# FPGA-2.net
KiCad netlist of a schematic drawn in Altium Designer
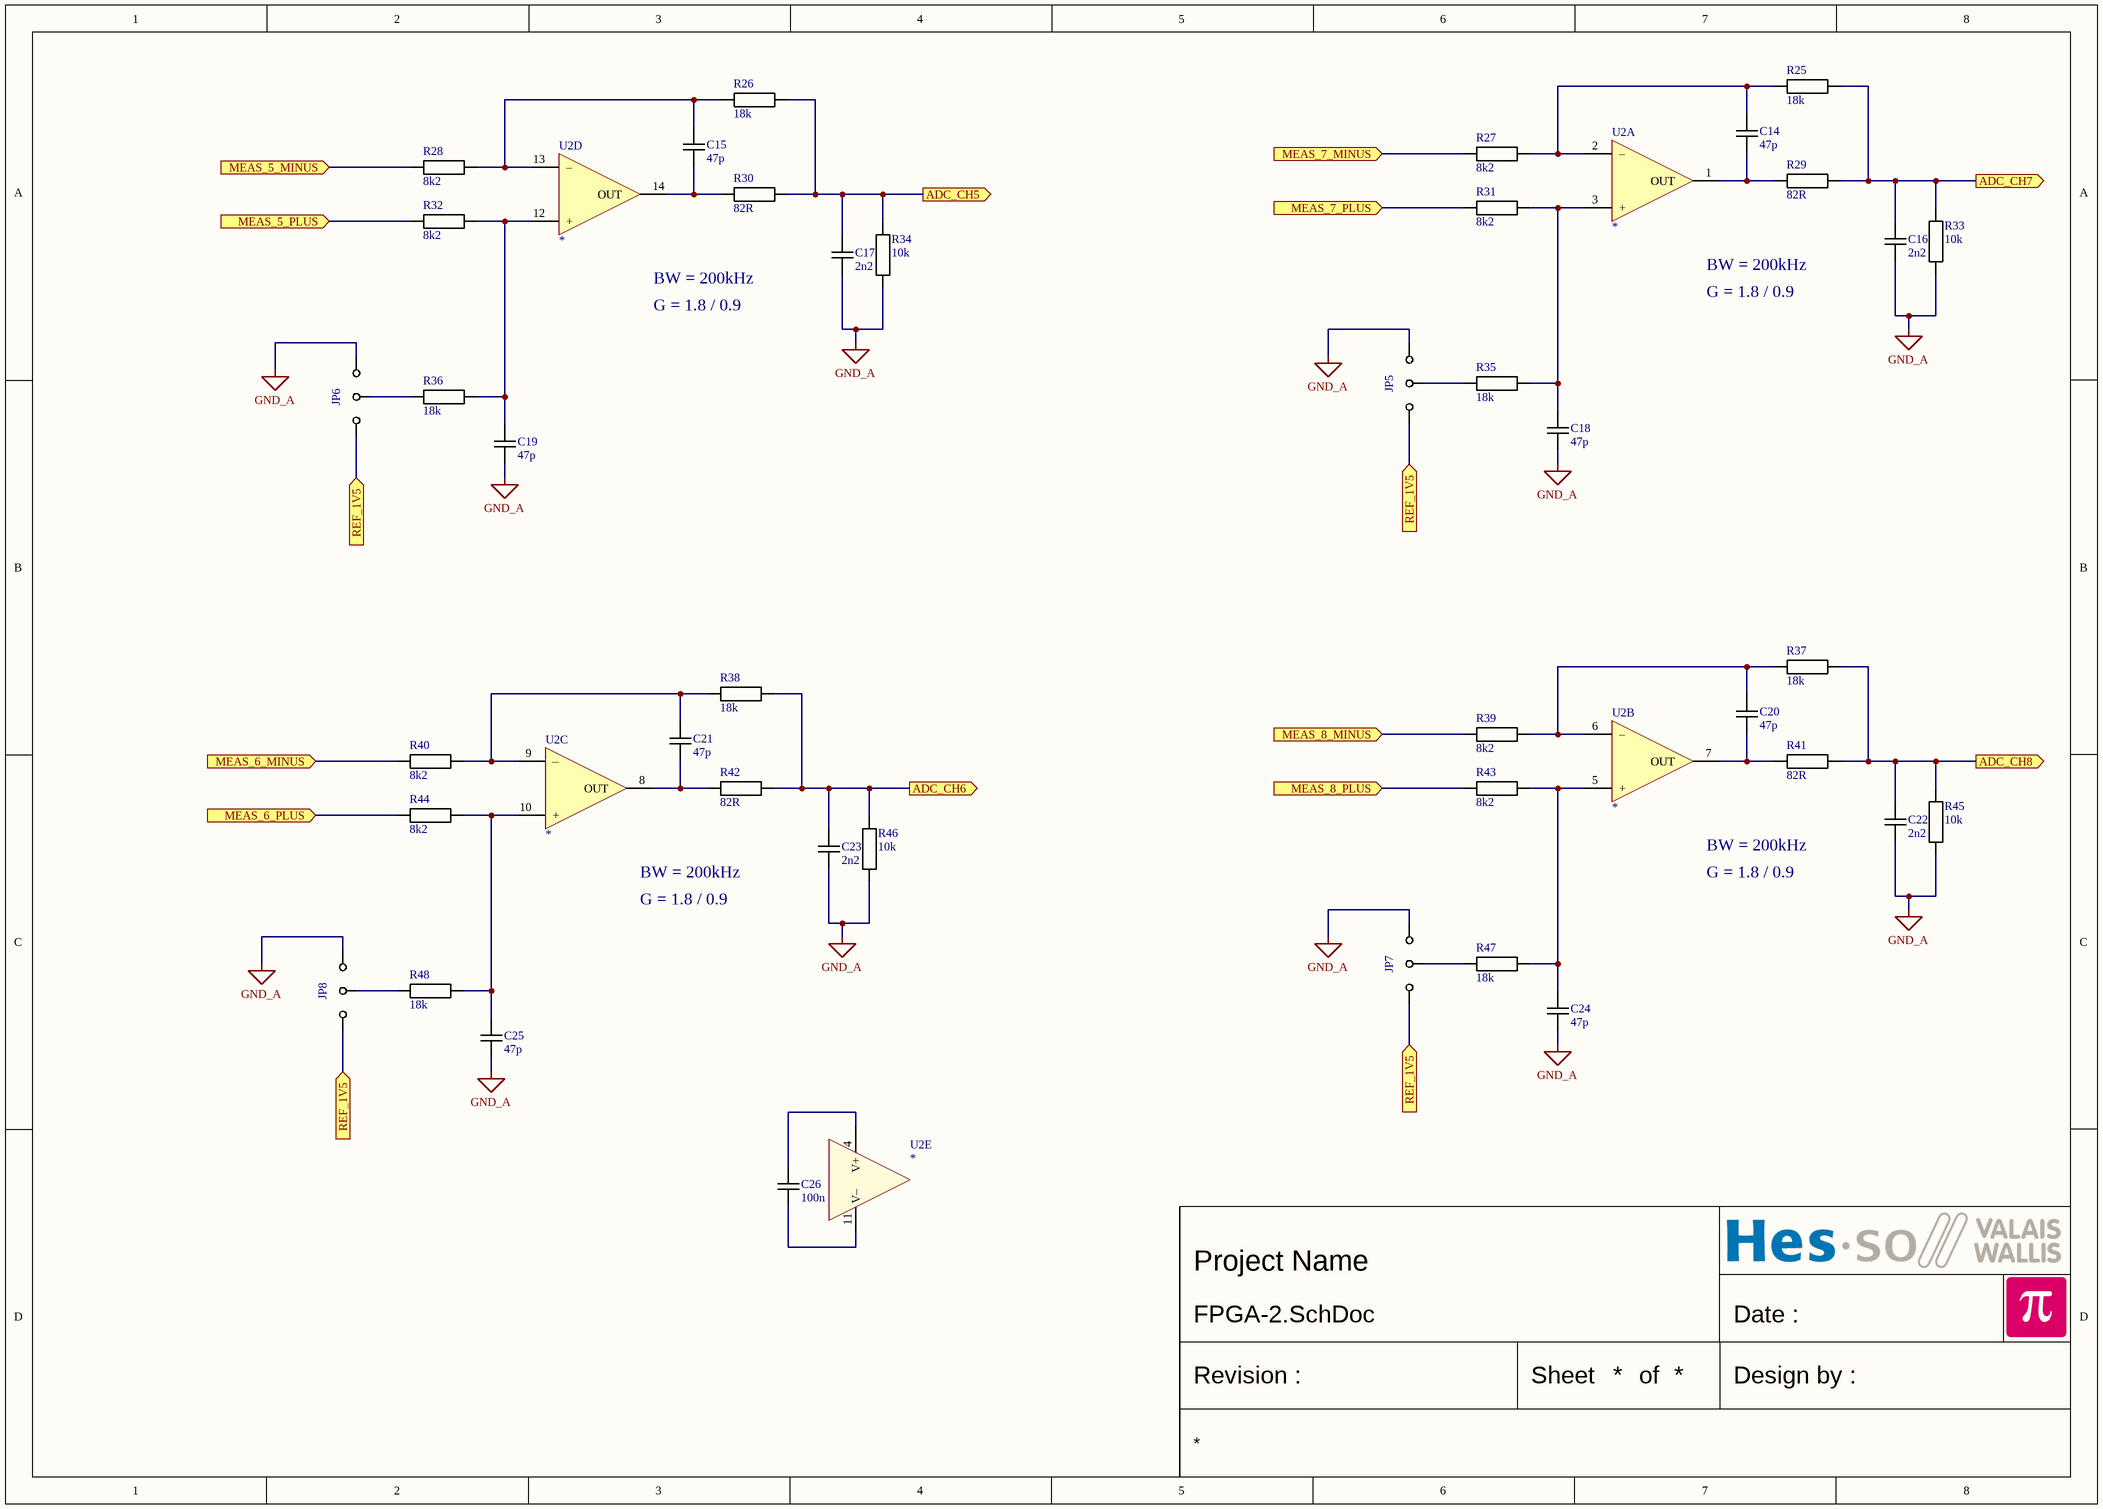
[diagram p0: FPGA-2.SchDoc]

(export (version "E")
  (design (tool "Eeschema 10.0.6"))
  (components
    (comp (ref "C14")
      (value "47p")
      (footprint "CAPACITOR 1608 REFLOW")
      (description "Capacitor X7R 10% 50V 1608(0603)")
      (libsource (lib "Capacitor") (part "Capacitor"))
    )
    (comp (ref "C15")
      (value "47p")
      (footprint "CAPACITOR 1608 REFLOW")
      (description "Capacitor X7R 10% 50V 1608(0603)")
      (libsource (lib "Capacitor") (part "Capacitor"))
    )
    (comp (ref "C16")
      (value "2n2")
      (footprint "CAPACITOR 1608 REFLOW")
      (description "Capacitor X7R 10% 50V 1608(0603)")
      (libsource (lib "Capacitor") (part "Capacitor"))
    )
    (comp (ref "C17")
      (value "2n2")
      (footprint "CAPACITOR 1608 REFLOW")
      (description "Capacitor X7R 10% 50V 1608(0603)")
      (libsource (lib "Capacitor") (part "Capacitor"))
    )
    (comp (ref "C18")
      (value "47p")
      (footprint "CAPACITOR 1608 REFLOW")
      (description "Capacitor X7R 10% 50V 1608(0603)")
      (libsource (lib "Capacitor") (part "Capacitor"))
    )
    (comp (ref "C19")
      (value "47p")
      (footprint "CAPACITOR 1608 REFLOW")
      (description "Capacitor X7R 10% 50V 1608(0603)")
      (libsource (lib "Capacitor") (part "Capacitor"))
    )
    (comp (ref "C20")
      (value "47p")
      (footprint "CAPACITOR 1608 REFLOW")
      (description "Capacitor X7R 10% 50V 1608(0603)")
      (libsource (lib "Capacitor") (part "Capacitor"))
    )
    (comp (ref "C21")
      (value "47p")
      (footprint "CAPACITOR 1608 REFLOW")
      (description "Capacitor X7R 10% 50V 1608(0603)")
      (libsource (lib "Capacitor") (part "Capacitor"))
    )
    (comp (ref "C22")
      (value "2n2")
      (footprint "CAPACITOR 1608 REFLOW")
      (description "Capacitor X7R 10% 50V 1608(0603)")
      (libsource (lib "Capacitor") (part "Capacitor"))
    )
    (comp (ref "C23")
      (value "2n2")
      (footprint "CAPACITOR 1608 REFLOW")
      (description "Capacitor X7R 10% 50V 1608(0603)")
      (libsource (lib "Capacitor") (part "Capacitor"))
    )
    (comp (ref "C24")
      (value "47p")
      (footprint "CAPACITOR 1608 REFLOW")
      (description "Capacitor X7R 10% 50V 1608(0603)")
      (libsource (lib "Capacitor") (part "Capacitor"))
    )
    (comp (ref "C25")
      (value "47p")
      (footprint "CAPACITOR 1608 REFLOW")
      (description "Capacitor X7R 10% 50V 1608(0603)")
      (libsource (lib "Capacitor") (part "Capacitor"))
    )
    (comp (ref "C26")
      (value "100n")
      (footprint "CAPACITOR 1608 REFLOW")
      (description "Capacitor X7R 10% 50V 1608(0603)")
      (libsource (lib "Capacitor") (part "Capacitor"))
    )
    (comp (ref "JP5")
      (value "{Value}")
      (footprint "JUMPER3 SMD 1608")
      (description "JUMPER 3 POS")
      (libsource (lib "Jumper") (part "JUMPER 3 POS"))
    )
    (comp (ref "JP6")
      (value "{Value}")
      (footprint "JUMPER3 SMD 1608")
      (description "JUMPER 3 POS")
      (libsource (lib "Jumper") (part "JUMPER 3 POS"))
    )
    (comp (ref "JP7")
      (value "{Value}")
      (footprint "JUMPER3 SMD 1608")
      (description "JUMPER 3 POS")
      (libsource (lib "Jumper") (part "JUMPER 3 POS"))
    )
    (comp (ref "JP8")
      (value "{Value}")
      (footprint "JUMPER3 SMD 1608")
      (description "JUMPER 3 POS")
      (libsource (lib "Jumper") (part "JUMPER 3 POS"))
    )
    (comp (ref "R25")
      (value "18k")
      (footprint "RESISTOR 1608 REFLOW")
      (description "Resistor 1% 50V 100mW 1608(0603)")
      (libsource (lib "Resistor") (part "Resistor"))
    )
    (comp (ref "R26")
      (value "18k")
      (footprint "RESISTOR 1608 REFLOW")
      (description "Resistor 1% 50V 100mW 1608(0603)")
      (libsource (lib "Resistor") (part "Resistor"))
    )
    (comp (ref "R27")
      (value "8k2")
      (footprint "RESISTOR 1608 REFLOW")
      (description "Resistor 1% 50V 100mW 1608(0603)")
      (libsource (lib "Resistor") (part "Resistor"))
    )
    (comp (ref "R28")
      (value "8k2")
      (footprint "RESISTOR 1608 REFLOW")
      (description "Resistor 1% 50V 100mW 1608(0603)")
      (libsource (lib "Resistor") (part "Resistor"))
    )
    (comp (ref "R29")
      (value "82R")
      (footprint "RESISTOR 1608 REFLOW")
      (description "Resistor 1% 50V 100mW 1608(0603)")
      (libsource (lib "Resistor") (part "Resistor"))
    )
    (comp (ref "R30")
      (value "82R")
      (footprint "RESISTOR 1608 REFLOW")
      (description "Resistor 1% 50V 100mW 1608(0603)")
      (libsource (lib "Resistor") (part "Resistor"))
    )
    (comp (ref "R31")
      (value "8k2")
      (footprint "RESISTOR 1608 REFLOW")
      (description "Resistor 1% 50V 100mW 1608(0603)")
      (libsource (lib "Resistor") (part "Resistor"))
    )
    (comp (ref "R32")
      (value "8k2")
      (footprint "RESISTOR 1608 REFLOW")
      (description "Resistor 1% 50V 100mW 1608(0603)")
      (libsource (lib "Resistor") (part "Resistor"))
    )
    (comp (ref "R33")
      (value "10k")
      (footprint "RESISTOR 1608 REFLOW")
      (description "Resistor 1% 50V 100mW 1608(0603)")
      (libsource (lib "Resistor") (part "Resistor"))
    )
    (comp (ref "R34")
      (value "10k")
      (footprint "RESISTOR 1608 REFLOW")
      (description "Resistor 1% 50V 100mW 1608(0603)")
      (libsource (lib "Resistor") (part "Resistor"))
    )
    (comp (ref "R35")
      (value "18k")
      (footprint "RESISTOR 1608 REFLOW")
      (description "Resistor 1% 50V 100mW 1608(0603)")
      (libsource (lib "Resistor") (part "Resistor"))
    )
    (comp (ref "R36")
      (value "18k")
      (footprint "RESISTOR 1608 REFLOW")
      (description "Resistor 1% 50V 100mW 1608(0603)")
      (libsource (lib "Resistor") (part "Resistor"))
    )
    (comp (ref "R37")
      (value "18k")
      (footprint "RESISTOR 1608 REFLOW")
      (description "Resistor 1% 50V 100mW 1608(0603)")
      (libsource (lib "Resistor") (part "Resistor"))
    )
    (comp (ref "R38")
      (value "18k")
      (footprint "RESISTOR 1608 REFLOW")
      (description "Resistor 1% 50V 100mW 1608(0603)")
      (libsource (lib "Resistor") (part "Resistor"))
    )
    (comp (ref "R39")
      (value "8k2")
      (footprint "RESISTOR 1608 REFLOW")
      (description "Resistor 1% 50V 100mW 1608(0603)")
      (libsource (lib "Resistor") (part "Resistor"))
    )
    (comp (ref "R40")
      (value "8k2")
      (footprint "RESISTOR 1608 REFLOW")
      (description "Resistor 1% 50V 100mW 1608(0603)")
      (libsource (lib "Resistor") (part "Resistor"))
    )
    (comp (ref "R41")
      (value "82R")
      (footprint "RESISTOR 1608 REFLOW")
      (description "Resistor 1% 50V 100mW 1608(0603)")
      (libsource (lib "Resistor") (part "Resistor"))
    )
    (comp (ref "R42")
      (value "82R")
      (footprint "RESISTOR 1608 REFLOW")
      (description "Resistor 1% 50V 100mW 1608(0603)")
      (libsource (lib "Resistor") (part "Resistor"))
    )
    (comp (ref "R43")
      (value "8k2")
      (footprint "RESISTOR 1608 REFLOW")
      (description "Resistor 1% 50V 100mW 1608(0603)")
      (libsource (lib "Resistor") (part "Resistor"))
    )
    (comp (ref "R44")
      (value "8k2")
      (footprint "RESISTOR 1608 REFLOW")
      (description "Resistor 1% 50V 100mW 1608(0603)")
      (libsource (lib "Resistor") (part "Resistor"))
    )
    (comp (ref "R45")
      (value "10k")
      (footprint "RESISTOR 1608 REFLOW")
      (description "Resistor 1% 50V 100mW 1608(0603)")
      (libsource (lib "Resistor") (part "Resistor"))
    )
    (comp (ref "R46")
      (value "10k")
      (footprint "RESISTOR 1608 REFLOW")
      (description "Resistor 1% 50V 100mW 1608(0603)")
      (libsource (lib "Resistor") (part "Resistor"))
    )
    (comp (ref "R47")
      (value "18k")
      (footprint "RESISTOR 1608 REFLOW")
      (description "Resistor 1% 50V 100mW 1608(0603)")
      (libsource (lib "Resistor") (part "Resistor"))
    )
    (comp (ref "R48")
      (value "18k")
      (footprint "RESISTOR 1608 REFLOW")
      (description "Resistor 1% 50V 100mW 1608(0603)")
      (libsource (lib "Resistor") (part "Resistor"))
    )
    (comp (ref "U2")
      (value "*")
      (footprint "SO14 P1.27 C4.0X8.8 H1.75")
      (description "Generic quad OPA 14 pins")
      (libsource (lib "Amplifier") (part "OPA QUAD"))
    )
  )
  (nets
    (net (code "1") (name "/ADC_CH5") (class "Default")
      (node (ref "C17") (pin "2") (pinfunction "2_2") (pintype "passive"))
      (node (ref "R26") (pin "2") (pinfunction "2_2") (pintype "passive"))
      (node (ref "R30") (pin "2") (pinfunction "2_2") (pintype "passive"))
      (node (ref "R34") (pin "1") (pinfunction "1_1") (pintype "passive"))
    )
    (net (code "2") (name "/ADC_CH6") (class "Default")
      (node (ref "C23") (pin "2") (pinfunction "2_2") (pintype "passive"))
      (node (ref "R38") (pin "2") (pinfunction "2_2") (pintype "passive"))
      (node (ref "R42") (pin "2") (pinfunction "2_2") (pintype "passive"))
      (node (ref "R46") (pin "1") (pinfunction "1_1") (pintype "passive"))
    )
    (net (code "3") (name "/ADC_CH7") (class "Default")
      (node (ref "C16") (pin "2") (pinfunction "2_2") (pintype "passive"))
      (node (ref "R25") (pin "2") (pinfunction "2_2") (pintype "passive"))
      (node (ref "R29") (pin "2") (pinfunction "2_2") (pintype "passive"))
      (node (ref "R33") (pin "1") (pinfunction "1_1") (pintype "passive"))
    )
    (net (code "4") (name "/ADC_CH8") (class "Default")
      (node (ref "C22") (pin "2") (pinfunction "2_2") (pintype "passive"))
      (node (ref "R37") (pin "2") (pinfunction "2_2") (pintype "passive"))
      (node (ref "R41") (pin "2") (pinfunction "2_2") (pintype "passive"))
      (node (ref "R45") (pin "1") (pinfunction "1_1") (pintype "passive"))
    )
    (net (code "5") (name "/MEAS_5_MINUS") (class "Default")
      (node (ref "R28") (pin "1") (pinfunction "1_1") (pintype "passive"))
    )
    (net (code "6") (name "/MEAS_5_PLUS") (class "Default")
      (node (ref "R32") (pin "1") (pinfunction "1_1") (pintype "passive"))
    )
    (net (code "7") (name "/MEAS_6_MINUS") (class "Default")
      (node (ref "R40") (pin "1") (pinfunction "1_1") (pintype "passive"))
    )
    (net (code "8") (name "/MEAS_6_PLUS") (class "Default")
      (node (ref "R44") (pin "1") (pinfunction "1_1") (pintype "passive"))
    )
    (net (code "9") (name "/MEAS_7_MINUS") (class "Default")
      (node (ref "R27") (pin "1") (pinfunction "1_1") (pintype "passive"))
    )
    (net (code "10") (name "/MEAS_7_PLUS") (class "Default")
      (node (ref "R31") (pin "1") (pinfunction "1_1") (pintype "passive"))
    )
    (net (code "11") (name "/MEAS_8_MINUS") (class "Default")
      (node (ref "R39") (pin "1") (pinfunction "1_1") (pintype "passive"))
    )
    (net (code "12") (name "/MEAS_8_PLUS") (class "Default")
      (node (ref "R43") (pin "1") (pinfunction "1_1") (pintype "passive"))
    )
    (net (code "13") (name "/REF_1V5") (class "Default")
      (node (ref "JP5") (pin "1") (pinfunction "1_1") (pintype "passive"))
      (node (ref "JP6") (pin "1") (pinfunction "1_1") (pintype "passive"))
      (node (ref "JP7") (pin "1") (pinfunction "1_1") (pintype "passive"))
      (node (ref "JP8") (pin "1") (pinfunction "1_1") (pintype "passive"))
    )
    (net (code "14") (name "GND_A") (class "Default")
      (node (ref "C16") (pin "1") (pinfunction "1_1") (pintype "passive"))
      (node (ref "C17") (pin "1") (pinfunction "1_1") (pintype "passive"))
      (node (ref "C18") (pin "1") (pinfunction "1_1") (pintype "passive"))
      (node (ref "C19") (pin "1") (pinfunction "1_1") (pintype "passive"))
      (node (ref "C22") (pin "1") (pinfunction "1_1") (pintype "passive"))
      (node (ref "C23") (pin "1") (pinfunction "1_1") (pintype "passive"))
      (node (ref "C24") (pin "1") (pinfunction "1_1") (pintype "passive"))
      (node (ref "C25") (pin "1") (pinfunction "1_1") (pintype "passive"))
      (node (ref "JP5") (pin "3") (pinfunction "3_3") (pintype "passive"))
      (node (ref "JP6") (pin "3") (pinfunction "3_3") (pintype "passive"))
      (node (ref "JP7") (pin "3") (pinfunction "3_3") (pintype "passive"))
      (node (ref "JP8") (pin "3") (pinfunction "3_3") (pintype "passive"))
      (node (ref "R33") (pin "2") (pinfunction "2_2") (pintype "passive"))
      (node (ref "R34") (pin "2") (pinfunction "2_2") (pintype "passive"))
      (node (ref "R45") (pin "2") (pinfunction "2_2") (pintype "passive"))
      (node (ref "R46") (pin "2") (pinfunction "2_2") (pintype "passive"))
    )
    (net (code "15") (name "Net-(JP5-Pad2)") (class "Default")
      (node (ref "JP5") (pin "2") (pinfunction "2_2") (pintype "passive"))
      (node (ref "R35") (pin "2") (pinfunction "2_2") (pintype "passive"))
    )
    (net (code "16") (name "Net-(JP6-Pad2)") (class "Default")
      (node (ref "JP6") (pin "2") (pinfunction "2_2") (pintype "passive"))
      (node (ref "R36") (pin "2") (pinfunction "2_2") (pintype "passive"))
    )
    (net (code "17") (name "Net-(JP7-Pad2)") (class "Default")
      (node (ref "JP7") (pin "2") (pinfunction "2_2") (pintype "passive"))
      (node (ref "R47") (pin "2") (pinfunction "2_2") (pintype "passive"))
    )
    (net (code "18") (name "Net-(JP8-Pad2)") (class "Default")
      (node (ref "JP8") (pin "2") (pinfunction "2_2") (pintype "passive"))
      (node (ref "R48") (pin "2") (pinfunction "2_2") (pintype "passive"))
    )
    (net (code "19") (name "Net-(U2A-+)") (class "Default")
      (node (ref "C18") (pin "2") (pinfunction "2_2") (pintype "passive"))
      (node (ref "R31") (pin "2") (pinfunction "2_2") (pintype "passive"))
      (node (ref "R35") (pin "1") (pinfunction "1_1") (pintype "passive"))
      (node (ref "U2") (pin "3") (pinfunction "+_3") (pintype "passive"))
    )
    (net (code "20") (name "Net-(U2A-OUT)") (class "Default")
      (node (ref "C14") (pin "1") (pinfunction "1_1") (pintype "passive"))
      (node (ref "R29") (pin "1") (pinfunction "1_1") (pintype "passive"))
      (node (ref "U2") (pin "1") (pinfunction "OUT_1") (pintype "passive"))
    )
    (net (code "21") (name "Net-(U2A-–)") (class "Default")
      (node (ref "C14") (pin "2") (pinfunction "2_2") (pintype "passive"))
      (node (ref "R25") (pin "1") (pinfunction "1_1") (pintype "passive"))
      (node (ref "R27") (pin "2") (pinfunction "2_2") (pintype "passive"))
      (node (ref "U2") (pin "2") (pinfunction "–_2") (pintype "passive"))
    )
    (net (code "22") (name "Net-(U2B-+)") (class "Default")
      (node (ref "C24") (pin "2") (pinfunction "2_2") (pintype "passive"))
      (node (ref "R43") (pin "2") (pinfunction "2_2") (pintype "passive"))
      (node (ref "R47") (pin "1") (pinfunction "1_1") (pintype "passive"))
      (node (ref "U2") (pin "5") (pinfunction "+_5") (pintype "passive"))
    )
    (net (code "23") (name "Net-(U2B-OUT)") (class "Default")
      (node (ref "C20") (pin "1") (pinfunction "1_1") (pintype "passive"))
      (node (ref "R41") (pin "1") (pinfunction "1_1") (pintype "passive"))
      (node (ref "U2") (pin "7") (pinfunction "OUT_7") (pintype "passive"))
    )
    (net (code "24") (name "Net-(U2B-–)") (class "Default")
      (node (ref "C20") (pin "2") (pinfunction "2_2") (pintype "passive"))
      (node (ref "R37") (pin "1") (pinfunction "1_1") (pintype "passive"))
      (node (ref "R39") (pin "2") (pinfunction "2_2") (pintype "passive"))
      (node (ref "U2") (pin "6") (pinfunction "–_6") (pintype "passive"))
    )
    (net (code "25") (name "Net-(U2C-+)") (class "Default")
      (node (ref "C25") (pin "2") (pinfunction "2_2") (pintype "passive"))
      (node (ref "R44") (pin "2") (pinfunction "2_2") (pintype "passive"))
      (node (ref "R48") (pin "1") (pinfunction "1_1") (pintype "passive"))
      (node (ref "U2") (pin "10") (pinfunction "+_10") (pintype "passive"))
    )
    (net (code "26") (name "Net-(U2C-OUT)") (class "Default")
      (node (ref "C21") (pin "1") (pinfunction "1_1") (pintype "passive"))
      (node (ref "R42") (pin "1") (pinfunction "1_1") (pintype "passive"))
      (node (ref "U2") (pin "8") (pinfunction "OUT_8") (pintype "passive"))
    )
    (net (code "27") (name "Net-(U2C-–)") (class "Default")
      (node (ref "C21") (pin "2") (pinfunction "2_2") (pintype "passive"))
      (node (ref "R38") (pin "1") (pinfunction "1_1") (pintype "passive"))
      (node (ref "R40") (pin "2") (pinfunction "2_2") (pintype "passive"))
      (node (ref "U2") (pin "9") (pinfunction "–_9") (pintype "passive"))
    )
    (net (code "28") (name "Net-(U2D-+)") (class "Default")
      (node (ref "C19") (pin "2") (pinfunction "2_2") (pintype "passive"))
      (node (ref "R32") (pin "2") (pinfunction "2_2") (pintype "passive"))
      (node (ref "R36") (pin "1") (pinfunction "1_1") (pintype "passive"))
      (node (ref "U2") (pin "12") (pinfunction "+_12") (pintype "passive"))
    )
    (net (code "29") (name "Net-(U2D-OUT)") (class "Default")
      (node (ref "C15") (pin "1") (pinfunction "1_1") (pintype "passive"))
      (node (ref "R30") (pin "1") (pinfunction "1_1") (pintype "passive"))
      (node (ref "U2") (pin "14") (pinfunction "OUT_14") (pintype "passive"))
    )
    (net (code "30") (name "Net-(U2D-–)") (class "Default")
      (node (ref "C15") (pin "2") (pinfunction "2_2") (pintype "passive"))
      (node (ref "R26") (pin "1") (pinfunction "1_1") (pintype "passive"))
      (node (ref "R28") (pin "2") (pinfunction "2_2") (pintype "passive"))
      (node (ref "U2") (pin "13") (pinfunction "–_13") (pintype "passive"))
    )
    (net (code "31") (name "Net-(U2E-V+)") (class "Default")
      (node (ref "C26") (pin "2") (pinfunction "2_2") (pintype "passive"))
      (node (ref "U2") (pin "4") (pinfunction "V+_4") (pintype "passive"))
    )
    (net (code "32") (name "Net-(U2E-V–)") (class "Default")
      (node (ref "C26") (pin "1") (pinfunction "1_1") (pintype "passive"))
      (node (ref "U2") (pin "11") (pinfunction "V–_11") (pintype "passive"))
    )
  )
)
